# 03-Intel_CPLD_0.net
KiCad netlist of a schematic drawn in Altium Designer
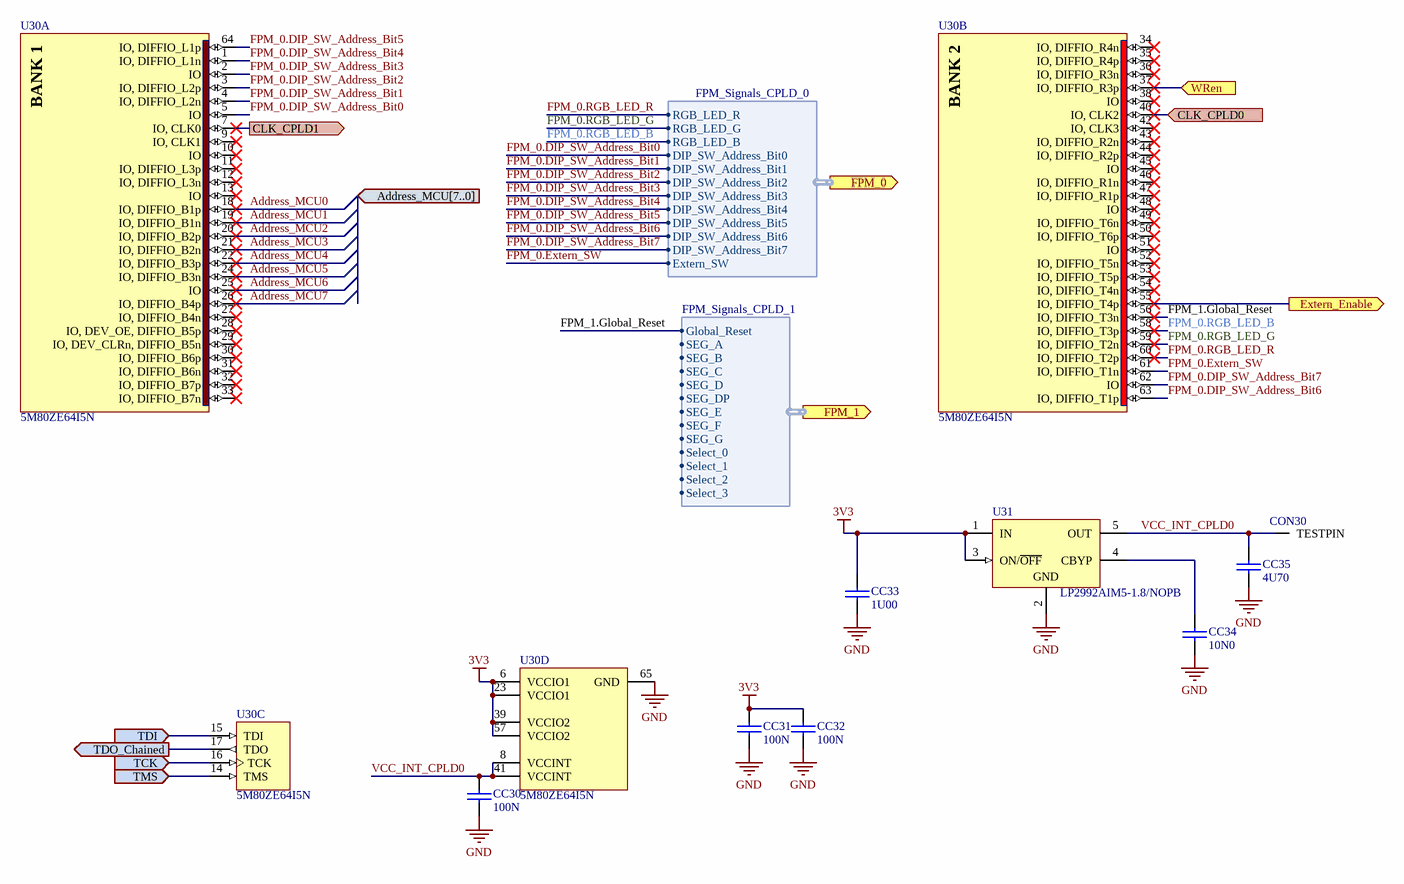
[diagram p0: 03-Intel_CPLD_0.SchDoc]

(export (version "E")
  (design (tool "Eeschema 10.0.6"))
  (components
    (comp (ref "CC30")
      (value "CC")
      (footprint "0603_C")
      (fields
        (field (name "CAPACITANCE") "100N")
        (field (name "MANUFACTURER") "Yageo")
        (field (name "TOLERANCE") "10P0")
      )
      (libsource (lib "Bauteildb") (part "CC"))
    )
    (comp (ref "CC31")
      (value "CC")
      (footprint "0603_C")
      (fields
        (field (name "CAPACITANCE") "100N")
        (field (name "MANUFACTURER") "Yageo")
        (field (name "TOLERANCE") "10P0")
      )
      (libsource (lib "Bauteildb") (part "CC"))
    )
    (comp (ref "CC32")
      (value "CC")
      (footprint "0603_C")
      (fields
        (field (name "CAPACITANCE") "100N")
        (field (name "MANUFACTURER") "Yageo")
        (field (name "TOLERANCE") "10P0")
      )
      (libsource (lib "Bauteildb") (part "CC"))
    )
    (comp (ref "CC33")
      (value "CC")
      (footprint "0603_C")
      (fields
        (field (name "CAPACITANCE") "1U00")
        (field (name "MANUFACTURER") "Taiyo Yuden")
        (field (name "TOLERANCE") "10P0")
      )
      (libsource (lib "Bauteildb") (part "CC"))
    )
    (comp (ref "CC34")
      (value "CC")
      (footprint "0603_C")
      (fields
        (field (name "CAPACITANCE") "10N0")
        (field (name "MANUFACTURER") "Kemet")
        (field (name "TOLERANCE") "10P0")
      )
      (libsource (lib "Bauteildb") (part "CC"))
    )
    (comp (ref "CC35")
      (value "CC")
      (footprint "0603_C")
      (fields
        (field (name "CAPACITANCE") "4U70")
        (field (name "MANUFACTURER") "Samsung")
        (field (name "TOLERANCE") "10P0")
      )
      (libsource (lib "Bauteildb") (part "CC"))
    )
    (comp (ref "CON30")
      (value "CON_001_M_MM000_S_X_MILL-MAX_TP")
      (footprint "CON_001_THT_MM000_S_D")
      (description "MILL-MAX_TP")
      (fields (field (name "MANUFACTURER") "MILL-MAX") (field (name "EDITOR_DATE") "boos, 06.02.2014"))
      (libsource (lib "Bauteildb") (part "CON_001_M_MM000_S_X_MILL-MAX_TP"))
    )
    (comp (ref "U30")
      (value "5M80ZE64I5N")
      (footprint "EQFP64_A-120_D2-45_M")
      (libsource (lib "Altium Content Vault") (part "PLD-ALMAX5-5M80Z-SQ64"))
    )
    (comp (ref "U31")
      (value "LP2992AIM5-1.8/NOPB")
      (footprint "MF05A_N")
      (description "Micropower 250 mA Low-Noise Ultra Low-Dropout Regulator, 5-pin SOT-23, Pb-Free")
      (fields (field (name "MANUFACTURER") "National Semiconductor"))
      (libsource (lib "Altium Content Vault") (part "PM-REG-LP2985-SOT5"))
    )
  )
  (nets
    (net (code "3") (name "/Address_MCU0") (class "Default")
      (node (ref "U30") (pin "18") (pinfunction "IO,_DIFFIO_B1p_18") (pintype "bidirectional+no_connect"))
    )
    (net (code "4") (name "/Address_MCU1") (class "Default")
      (node (ref "U30") (pin "19") (pinfunction "IO,_DIFFIO_B1n_19") (pintype "bidirectional+no_connect"))
    )
    (net (code "5") (name "/Address_MCU2") (class "Default")
      (node (ref "U30") (pin "20") (pinfunction "IO,_DIFFIO_B2p_20") (pintype "bidirectional+no_connect"))
    )
    (net (code "6") (name "/Address_MCU3") (class "Default")
      (node (ref "U30") (pin "21") (pinfunction "IO,_DIFFIO_B2n_21") (pintype "bidirectional+no_connect"))
    )
    (net (code "7") (name "/Address_MCU4") (class "Default")
      (node (ref "U30") (pin "22") (pinfunction "IO,_DIFFIO_B3p_22") (pintype "bidirectional+no_connect"))
    )
    (net (code "8") (name "/Address_MCU5") (class "Default")
      (node (ref "U30") (pin "24") (pinfunction "IO,_DIFFIO_B3n_24") (pintype "bidirectional+no_connect"))
    )
    (net (code "9") (name "/Address_MCU6") (class "Default")
      (node (ref "U30") (pin "25") (pinfunction "IO_25") (pintype "bidirectional+no_connect"))
    )
    (net (code "10") (name "/Address_MCU7") (class "Default")
      (node (ref "U30") (pin "26") (pinfunction "IO,_DIFFIO_B4p_26") (pintype "bidirectional+no_connect"))
    )
    (net (code "12") (name "/CLK_CPLD0") (class "Default")
      (node (ref "U30") (pin "40") (pinfunction "IO,_CLK2_40") (pintype "bidirectional+no_connect"))
    )
    (net (code "13") (name "/CLK_CPLD1") (class "Default")
      (node (ref "U30") (pin "7") (pinfunction "IO,_CLK0_7") (pintype "bidirectional+no_connect"))
    )
    (net (code "14") (name "/Extern_Enable") (class "Default")
      (node (ref "U30") (pin "55") (pinfunction "IO,_DIFFIO_T4p_55") (pintype "bidirectional+no_connect"))
    )
    (net (code "15") (name "/FPM_0.DIP_SW_Address_Bit0") (class "Default")
      (node (ref "U30") (pin "5") (pinfunction "IO_5") (pintype "bidirectional"))
    )
    (net (code "16") (name "/FPM_0.DIP_SW_Address_Bit1") (class "Default")
      (node (ref "U30") (pin "4") (pinfunction "IO,_DIFFIO_L2n_4") (pintype "bidirectional"))
    )
    (net (code "17") (name "/FPM_0.DIP_SW_Address_Bit2") (class "Default")
      (node (ref "U30") (pin "3") (pinfunction "IO,_DIFFIO_L2p_3") (pintype "bidirectional"))
    )
    (net (code "18") (name "/FPM_0.DIP_SW_Address_Bit3") (class "Default")
      (node (ref "U30") (pin "2") (pinfunction "IO_2") (pintype "bidirectional"))
    )
    (net (code "19") (name "/FPM_0.DIP_SW_Address_Bit4") (class "Default")
      (node (ref "U30") (pin "1") (pinfunction "IO,_DIFFIO_L1n_1") (pintype "bidirectional"))
    )
    (net (code "20") (name "/FPM_0.DIP_SW_Address_Bit5") (class "Default")
      (node (ref "U30") (pin "64") (pinfunction "IO,_DIFFIO_L1p_64") (pintype "bidirectional"))
    )
    (net (code "21") (name "/FPM_0.DIP_SW_Address_Bit6") (class "Default")
      (node (ref "U30") (pin "63") (pinfunction "IO,_DIFFIO_T1p_63") (pintype "bidirectional"))
    )
    (net (code "22") (name "/FPM_0.DIP_SW_Address_Bit7") (class "Default")
      (node (ref "U30") (pin "62") (pinfunction "IO_62") (pintype "bidirectional"))
    )
    (net (code "23") (name "/FPM_0.Extern_SW") (class "Default")
      (node (ref "U30") (pin "61") (pinfunction "IO,_DIFFIO_T1n_61") (pintype "bidirectional"))
    )
    (net (code "24") (name "/FPM_0.RGB_LED_B") (class "Default")
      (node (ref "U30") (pin "58") (pinfunction "IO,_DIFFIO_T3p_58") (pintype "bidirectional+no_connect"))
    )
    (net (code "25") (name "/FPM_0.RGB_LED_G") (class "Default")
      (node (ref "U30") (pin "59") (pinfunction "IO,_DIFFIO_T2n_59") (pintype "bidirectional+no_connect"))
    )
    (net (code "26") (name "/FPM_0.RGB_LED_R") (class "Default")
      (node (ref "U30") (pin "60") (pinfunction "IO,_DIFFIO_T2p_60") (pintype "bidirectional+no_connect"))
    )
    (net (code "27") (name "/FPM_1.Global_Reset") (class "Default")
      (node (ref "U30") (pin "56") (pinfunction "IO,_DIFFIO_T3n_56") (pintype "bidirectional+no_connect"))
    )
    (net (code "28") (name "/TCK") (class "Default")
      (node (ref "U30") (pin "16") (pinfunction "TCK_16") (pintype "input"))
    )
    (net (code "29") (name "/TDI") (class "Default")
      (node (ref "U30") (pin "15") (pinfunction "TDI_15") (pintype "input"))
    )
    (net (code "30") (name "/TDO_Chained") (class "Default")
      (node (ref "U30") (pin "17") (pinfunction "TDO_17") (pintype "output"))
    )
    (net (code "31") (name "/TMS") (class "Default")
      (node (ref "U30") (pin "14") (pinfunction "TMS_14") (pintype "input"))
    )
    (net (code "32") (name "/VCC_INT_CPLD0") (class "Default")
      (node (ref "CC30") (pin "2") (pintype "passive"))
      (node (ref "CC35") (pin "2") (pintype "passive"))
      (node (ref "CON30") (pin "1") (pinfunction "TESTPIN_1") (pintype "passive"))
      (node (ref "U30") (pin "41") (pinfunction "VCCINT_41") (pintype "power_in"))
      (node (ref "U30") (pin "8") (pinfunction "VCCINT_8") (pintype "power_in"))
      (node (ref "U31") (pin "5") (pinfunction "OUT_5") (pintype "power_in"))
    )
    (net (code "33") (name "/WRen") (class "Default")
      (node (ref "U30") (pin "37") (pinfunction "IO,_DIFFIO_R3p_37") (pintype "bidirectional+no_connect"))
    )
    (net (code "36") (name "3V3") (class "Default")
      (node (ref "CC31") (pin "2") (pintype "passive"))
      (node (ref "CC32") (pin "2") (pintype "passive"))
      (node (ref "CC33") (pin "2") (pintype "passive"))
      (node (ref "U30") (pin "23") (pinfunction "VCCIO1_23") (pintype "power_in"))
      (node (ref "U30") (pin "39") (pinfunction "VCCIO2_39") (pintype "power_in"))
      (node (ref "U30") (pin "57") (pinfunction "VCCIO2_57") (pintype "power_in"))
      (node (ref "U30") (pin "6") (pinfunction "VCCIO1_6") (pintype "power_in"))
      (node (ref "U31") (pin "1") (pinfunction "IN_1") (pintype "power_in"))
      (node (ref "U31") (pin "3") (pinfunction "ON/~{OFF}_3") (pintype "input"))
    )
    (net (code "37") (name "GND") (class "Default")
      (node (ref "CC30") (pin "1") (pintype "passive"))
      (node (ref "CC31") (pin "1") (pintype "passive"))
      (node (ref "CC32") (pin "1") (pintype "passive"))
      (node (ref "CC33") (pin "1") (pintype "passive"))
      (node (ref "CC34") (pin "1") (pintype "passive"))
      (node (ref "CC35") (pin "1") (pintype "passive"))
      (node (ref "U30") (pin "65") (pinfunction "GND_65") (pintype "power_in"))
      (node (ref "U31") (pin "2") (pinfunction "GND_2") (pintype "power_in"))
    )
    (net (code "38") (name "Net-(U31-CBYP)") (class "Default")
      (node (ref "CC34") (pin "2") (pintype "passive"))
      (node (ref "U31") (pin "4") (pinfunction "CBYP_4") (pintype "passive"))
    )
    (net (code "39") (name "unconnected-(U30A-IO,_CLK1-Pad9)") (class "Default")
      (node (ref "U30") (pin "9") (pinfunction "IO,_CLK1_9") (pintype "bidirectional+no_connect"))
    )
    (net (code "40") (name "unconnected-(U30A-IO,_DEV_CLRn,_DIFFIO_B5n-Pad29)") (class "Default")
      (node (ref "U30") (pin "29") (pinfunction "IO,_DEV_CLRn,_DIFFIO_B5n_29") (pintype "bidirectional+no_connect"))
    )
    (net (code "41") (name "unconnected-(U30A-IO,_DEV_OE,_DIFFIO_B5p-Pad28)") (class "Default")
      (node (ref "U30") (pin "28") (pinfunction "IO,_DEV_OE,_DIFFIO_B5p_28") (pintype "bidirectional+no_connect"))
    )
    (net (code "42") (name "unconnected-(U30A-IO,_DIFFIO_B4n-Pad27)") (class "Default")
      (node (ref "U30") (pin "27") (pinfunction "IO,_DIFFIO_B4n_27") (pintype "bidirectional+no_connect"))
    )
    (net (code "43") (name "unconnected-(U30A-IO,_DIFFIO_B6n-Pad31)") (class "Default")
      (node (ref "U30") (pin "31") (pinfunction "IO,_DIFFIO_B6n_31") (pintype "bidirectional+no_connect"))
    )
    (net (code "44") (name "unconnected-(U30A-IO,_DIFFIO_B6p-Pad30)") (class "Default")
      (node (ref "U30") (pin "30") (pinfunction "IO,_DIFFIO_B6p_30") (pintype "bidirectional+no_connect"))
    )
    (net (code "45") (name "unconnected-(U30A-IO,_DIFFIO_B7n-Pad33)") (class "Default")
      (node (ref "U30") (pin "33") (pinfunction "IO,_DIFFIO_B7n_33") (pintype "bidirectional+no_connect"))
    )
    (net (code "46") (name "unconnected-(U30A-IO,_DIFFIO_B7p-Pad32)") (class "Default")
      (node (ref "U30") (pin "32") (pinfunction "IO,_DIFFIO_B7p_32") (pintype "bidirectional+no_connect"))
    )
    (net (code "47") (name "unconnected-(U30A-IO,_DIFFIO_L3n-Pad12)") (class "Default")
      (node (ref "U30") (pin "12") (pinfunction "IO,_DIFFIO_L3n_12") (pintype "bidirectional+no_connect"))
    )
    (net (code "48") (name "unconnected-(U30A-IO,_DIFFIO_L3p-Pad11)") (class "Default")
      (node (ref "U30") (pin "11") (pinfunction "IO,_DIFFIO_L3p_11") (pintype "bidirectional+no_connect"))
    )
    (net (code "49") (name "unconnected-(U30A-IO-Pad10)") (class "Default")
      (node (ref "U30") (pin "10") (pinfunction "IO_10") (pintype "bidirectional+no_connect"))
    )
    (net (code "50") (name "unconnected-(U30A-IO-Pad13)") (class "Default")
      (node (ref "U30") (pin "13") (pinfunction "IO_13") (pintype "bidirectional+no_connect"))
    )
    (net (code "51") (name "unconnected-(U30B-IO,_CLK3-Pad42)") (class "Default")
      (node (ref "U30") (pin "42") (pinfunction "IO,_CLK3_42") (pintype "bidirectional+no_connect"))
    )
    (net (code "52") (name "unconnected-(U30B-IO,_DIFFIO_R1n-Pad46)") (class "Default")
      (node (ref "U30") (pin "46") (pinfunction "IO,_DIFFIO_R1n_46") (pintype "bidirectional+no_connect"))
    )
    (net (code "53") (name "unconnected-(U30B-IO,_DIFFIO_R1p-Pad47)") (class "Default")
      (node (ref "U30") (pin "47") (pinfunction "IO,_DIFFIO_R1p_47") (pintype "bidirectional+no_connect"))
    )
    (net (code "54") (name "unconnected-(U30B-IO,_DIFFIO_R2n-Pad43)") (class "Default")
      (node (ref "U30") (pin "43") (pinfunction "IO,_DIFFIO_R2n_43") (pintype "bidirectional+no_connect"))
    )
    (net (code "55") (name "unconnected-(U30B-IO,_DIFFIO_R2p-Pad44)") (class "Default")
      (node (ref "U30") (pin "44") (pinfunction "IO,_DIFFIO_R2p_44") (pintype "bidirectional+no_connect"))
    )
    (net (code "56") (name "unconnected-(U30B-IO,_DIFFIO_R3n-Pad36)") (class "Default")
      (node (ref "U30") (pin "36") (pinfunction "IO,_DIFFIO_R3n_36") (pintype "bidirectional+no_connect"))
    )
    (net (code "57") (name "unconnected-(U30B-IO,_DIFFIO_R4n-Pad34)") (class "Default")
      (node (ref "U30") (pin "34") (pinfunction "IO,_DIFFIO_R4n_34") (pintype "bidirectional+no_connect"))
    )
    (net (code "58") (name "unconnected-(U30B-IO,_DIFFIO_R4p-Pad35)") (class "Default")
      (node (ref "U30") (pin "35") (pinfunction "IO,_DIFFIO_R4p_35") (pintype "bidirectional+no_connect"))
    )
    (net (code "59") (name "unconnected-(U30B-IO,_DIFFIO_T4n-Pad54)") (class "Default")
      (node (ref "U30") (pin "54") (pinfunction "IO,_DIFFIO_T4n_54") (pintype "bidirectional+no_connect"))
    )
    (net (code "60") (name "unconnected-(U30B-IO,_DIFFIO_T5n-Pad52)") (class "Default")
      (node (ref "U30") (pin "52") (pinfunction "IO,_DIFFIO_T5n_52") (pintype "bidirectional+no_connect"))
    )
    (net (code "61") (name "unconnected-(U30B-IO,_DIFFIO_T5p-Pad53)") (class "Default")
      (node (ref "U30") (pin "53") (pinfunction "IO,_DIFFIO_T5p_53") (pintype "bidirectional+no_connect"))
    )
    (net (code "62") (name "unconnected-(U30B-IO,_DIFFIO_T6n-Pad49)") (class "Default")
      (node (ref "U30") (pin "49") (pinfunction "IO,_DIFFIO_T6n_49") (pintype "bidirectional+no_connect"))
    )
    (net (code "63") (name "unconnected-(U30B-IO,_DIFFIO_T6p-Pad50)") (class "Default")
      (node (ref "U30") (pin "50") (pinfunction "IO,_DIFFIO_T6p_50") (pintype "bidirectional+no_connect"))
    )
    (net (code "64") (name "unconnected-(U30B-IO-Pad38)") (class "Default")
      (node (ref "U30") (pin "38") (pinfunction "IO_38") (pintype "bidirectional+no_connect"))
    )
    (net (code "65") (name "unconnected-(U30B-IO-Pad45)") (class "Default")
      (node (ref "U30") (pin "45") (pinfunction "IO_45") (pintype "bidirectional+no_connect"))
    )
    (net (code "66") (name "unconnected-(U30B-IO-Pad48)") (class "Default")
      (node (ref "U30") (pin "48") (pinfunction "IO_48") (pintype "bidirectional+no_connect"))
    )
    (net (code "67") (name "unconnected-(U30B-IO-Pad51)") (class "Default")
      (node (ref "U30") (pin "51") (pinfunction "IO_51") (pintype "bidirectional+no_connect"))
    )
  )
)
